# Top.net
KiCad netlist of a schematic drawn in Altium Designer
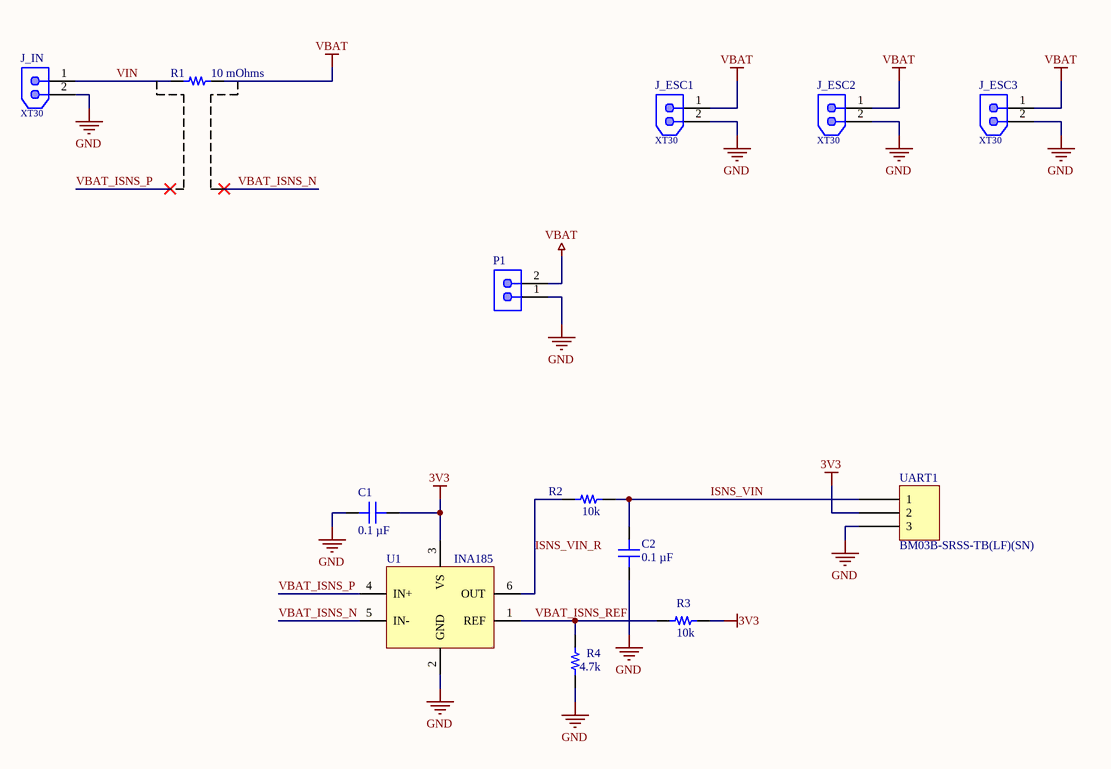
[diagram p0: Top.SchDoc]

(export (version "E")
  (design (tool "Eeschema 10.0.6"))
  (components
    (comp (ref "C1")
      (value "0.1 µF")
      (footprint "CAP 0402_1005")
      (description "CAP CER 0.1UF 16V X7R 0402")
      (fields (field (name "PART NUMBER") "C0402C104K4RACAUTO") (field (name "MANUFACTURER") "KEMET"))
      (libsource (lib "Celestial Altium Library - altium_library") (part "Capacitor"))
    )
    (comp (ref "C2")
      (value "0.1 µF")
      (footprint "CAP 0402_1005")
      (description "CAP CER 0.1UF 16V X7R 0402")
      (fields (field (name "PART NUMBER") "C0402C104K4RACAUTO") (field (name "MANUFACTURER") "KEMET"))
      (libsource (lib "Celestial Altium Library - altium_library") (part "Capacitor"))
    )
    (comp (ref "J_ESC1") (value "XT30") (footprint "XT30") (libsource (lib "IC") (part "XT30")))
    (comp (ref "J_ESC2") (value "XT30") (footprint "XT30") (libsource (lib "IC") (part "XT30")))
    (comp (ref "J_ESC3") (value "XT30") (footprint "XT30") (libsource (lib "IC") (part "XT30")))
    (comp (ref "J_IN") (value "XT30") (footprint "XT30") (libsource (lib "IC") (part "XT30")))
    (comp (ref "P1")
      (value "2 pin 2mm JST Male")
      (footprint "2pin - 2mm JST male")
      (libsource (lib "IC") (part "2 pin 2mm JST Male"))
    )
    (comp (ref "R1")
      (value "10 mOhms")
      (footprint "RES 1206_3216")
      (description "RES 0.039 OHM 1% 3/4W 1206")
      (fields (field (name "PART NUMBER") "KRL1632E-M-R039-F-T5") (field (name "MANUFACTURER") "Susumu"))
      (libsource (lib "Celestial Altium Library - altium_library") (part "Resistor"))
    )
    (comp (ref "R2")
      (value "10k")
      (footprint "RES_0402")
      (description "RES 0402")
      (libsource (lib "IC") (part "RES_0402"))
    )
    (comp (ref "R3")
      (value "10k")
      (footprint "RES_0402")
      (description "RES 0402")
      (libsource (lib "IC") (part "RES_0402"))
    )
    (comp (ref "R4")
      (value "4.7k")
      (footprint "RES_0402")
      (description "RES 0402")
      (libsource (lib "IC") (part "RES_0402"))
    )
    (comp (ref "U1")
      (value "INA185")
      (footprint "TI SC70-6 DCK")
      (description "INA185A2")
      (libsource (lib "IC") (part "INA185"))
    )
    (comp (ref "UART1")
      (value "BM03B-SRSS-TB(LF)(SN)")
      (footprint "JST BM03B-SRSS-TB")
      (description "CONN HEADER SMD 3POS 1MM")
      (fields (field (name "MANUFACTURER") "JST Sales America Inc."))
      (libsource (lib "Celestial Altium Library - altium_library") (part "3 Pin"))
    )
  )
  (nets
    (net (code "1") (name "/ISNS_VIN") (class "Default")
      (node (ref "C2") (pin "1") (pinfunction "1_1") (pintype "passive"))
      (node (ref "R2") (pin "1") (pinfunction "1_1") (pintype "passive"))
      (node (ref "UART1") (pin "1") (pinfunction "1_1") (pintype "passive"))
    )
    (net (code "2") (name "/ISNS_VIN_R") (class "Default")
      (node (ref "R2") (pin "2") (pinfunction "2_2") (pintype "passive"))
      (node (ref "U1") (pin "6") (pinfunction "OUT_6") (pintype "passive"))
    )
    (net (code "3") (name "/VBAT_ISNS_N") (class "Default")
      (node (ref "U1") (pin "5") (pinfunction "IN-_5") (pintype "passive+no_connect"))
    )
    (net (code "4") (name "/VBAT_ISNS_P") (class "Default")
      (node (ref "U1") (pin "4") (pinfunction "IN+_4") (pintype "passive+no_connect"))
    )
    (net (code "5") (name "/VBAT_ISNS_REF") (class "Default")
      (node (ref "R3") (pin "2") (pinfunction "2_2") (pintype "passive"))
      (node (ref "R4") (pin "1") (pinfunction "1_1") (pintype "passive"))
      (node (ref "U1") (pin "1") (pinfunction "REF_1") (pintype "passive"))
    )
    (net (code "6") (name "/VIN") (class "Default")
      (node (ref "J_IN") (pin "1") (pinfunction "1_1") (pintype "passive"))
      (node (ref "R1") (pin "1") (pinfunction "1_1") (pintype "passive"))
    )
    (net (code "7") (name "3V3") (class "Default")
      (node (ref "C1") (pin "1") (pinfunction "1_1") (pintype "passive"))
      (node (ref "R3") (pin "1") (pinfunction "1_1") (pintype "passive"))
      (node (ref "U1") (pin "3") (pinfunction "VS_3") (pintype "passive"))
      (node (ref "UART1") (pin "2") (pinfunction "2_2") (pintype "passive"))
    )
    (net (code "8") (name "GND") (class "Default")
      (node (ref "C1") (pin "2") (pinfunction "2_2") (pintype "passive"))
      (node (ref "C2") (pin "2") (pinfunction "2_2") (pintype "passive"))
      (node (ref "J_ESC1") (pin "2") (pinfunction "2_2") (pintype "passive"))
      (node (ref "J_ESC2") (pin "2") (pinfunction "2_2") (pintype "passive"))
      (node (ref "J_ESC3") (pin "2") (pinfunction "2_2") (pintype "passive"))
      (node (ref "J_IN") (pin "2") (pinfunction "2_2") (pintype "passive"))
      (node (ref "P1") (pin "1") (pinfunction "1_1") (pintype "passive"))
      (node (ref "R4") (pin "2") (pinfunction "2_2") (pintype "passive"))
      (node (ref "U1") (pin "2") (pinfunction "GND_2") (pintype "passive"))
      (node (ref "UART1") (pin "3") (pinfunction "3_3") (pintype "passive"))
    )
    (net (code "9") (name "VBAT") (class "Default")
      (node (ref "J_ESC1") (pin "1") (pinfunction "1_1") (pintype "passive"))
      (node (ref "J_ESC2") (pin "1") (pinfunction "1_1") (pintype "passive"))
      (node (ref "J_ESC3") (pin "1") (pinfunction "1_1") (pintype "passive"))
      (node (ref "P1") (pin "2") (pinfunction "2_2") (pintype "passive"))
      (node (ref "R1") (pin "2") (pinfunction "2_2") (pintype "passive"))
    )
  )
)
